# Oscillators.net
KiCad netlist of a schematic drawn in Altium Designer
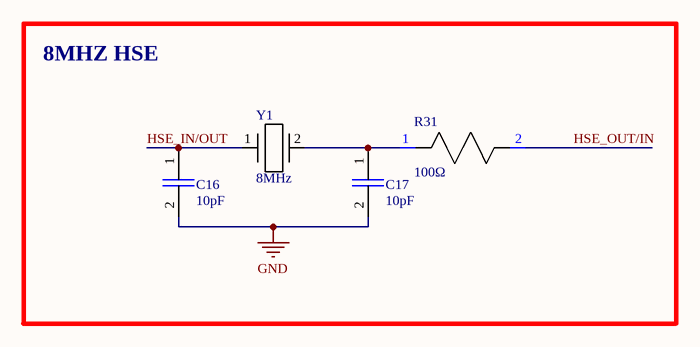
[diagram p0: Oscillators.SchDoc]

(export (version "E")
  (design (tool "Eeschema 10.0.6"))
  (components
    (comp (ref "C16")
      (value "10pF")
      (footprint "0603 Cap")
      (description "SMD 0603 (ceramic) capacitor")
      (fields
        (field (name "MANUFACTURER") "Murata")
        (field (name "MANUFACTURER PART NUMBER") "GRM21BR71C225KA12L")
      )
      (libsource (lib "Lib") (part "0603 Cap"))
    )
    (comp (ref "C17")
      (value "10pF")
      (footprint "0603 Cap")
      (description "SMD 0603 (ceramic) capacitor")
      (fields
        (field (name "MANUFACTURER") "Murata")
        (field (name "MANUFACTURER PART NUMBER") "GRM21BR71C225KA12L")
      )
      (libsource (lib "Lib") (part "0603 Cap"))
    )
    (comp (ref "R31")
      (value "100Ω")
      (footprint "0603 RES")
      (description "Can be used for SMD resistors")
      (fields (field (name "Comment") "Resistor"))
      (libsource (lib "Lib") (part "0603 Res"))
    )
    (comp (ref "Y1")
      (value "8MHz")
      (footprint "ABM3 2PIN SMD")
      (description "XTAL schematic. Footprint available for many packages")
      (fields (field (name "Comment") "XTAL"))
      (libsource (lib "Lib") (part "XTAL"))
    )
  )
  (nets
    (net (code "1") (name "/HSE_IN{slash}OUT") (class "Default")
      (node (ref "C16") (pin "1") (pinfunction "11_1") (pintype "passive"))
      (node (ref "Y1") (pin "1") (pinfunction "29_1") (pintype "passive"))
    )
    (net (code "2") (name "/HSE_OUT{slash}IN") (class "Default")
      (node (ref "R31") (pin "2") (pinfunction "21_2") (pintype "passive"))
    )
    (net (code "3") (name "GND") (class "Default")
      (node (ref "C16") (pin "2") (pinfunction "12_2") (pintype "passive"))
      (node (ref "C17") (pin "2") (pinfunction "12_2") (pintype "passive"))
    )
    (net (code "4") (name "Net-(C17-11)") (class "Default")
      (node (ref "C17") (pin "1") (pinfunction "11_1") (pintype "passive"))
      (node (ref "R31") (pin "1") (pinfunction "22_1") (pintype "passive"))
      (node (ref "Y1") (pin "2") (pinfunction "28_2") (pintype "passive"))
    )
  )
)
